# Keyboard_on_board.net
KiCad netlist of a schematic drawn in Altium Designer
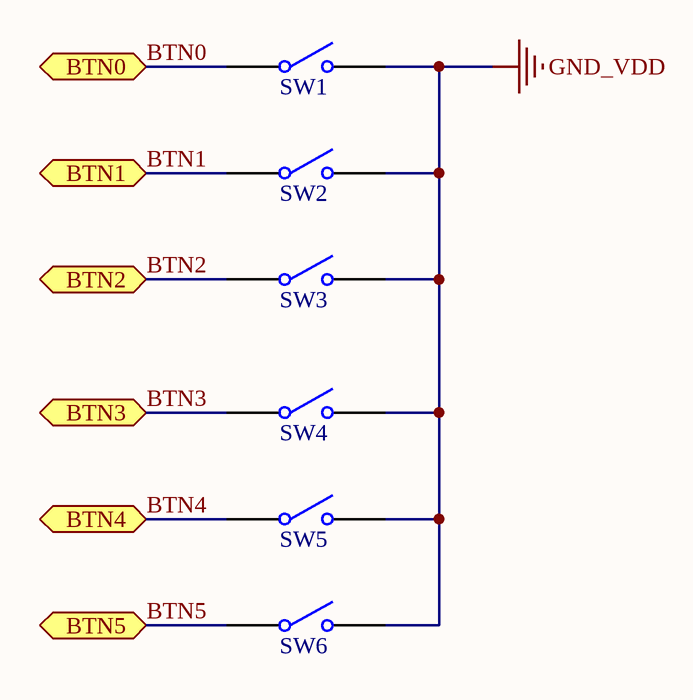
[diagram p0: Keyboard_on_board.SchDoc]

(export (version "E")
  (design (tool "Eeschema 10.0.6"))
  (components
    (comp (ref "SW1")
      (value "\"OK\"")
      (footprint "KAN1211")
      (description "Single-Pole, Single-Throw Switch")
      (fields (field (name "PUBLISHER") "Altium Limited"))
      (libsource (lib "Quasar ARM") (part "TACT Switch"))
    )
    (comp (ref "SW2")
      (value "\"Right\"")
      (footprint "KAN1211")
      (description "Single-Pole, Single-Throw Switch")
      (fields (field (name "PUBLISHER") "Altium Limited"))
      (libsource (lib "Quasar ARM") (part "TACT Switch"))
    )
    (comp (ref "SW3")
      (value "\"Down\"")
      (footprint "KAN1211")
      (description "Single-Pole, Single-Throw Switch")
      (fields (field (name "PUBLISHER") "Altium Limited"))
      (libsource (lib "Quasar ARM") (part "TACT Switch"))
    )
    (comp (ref "SW4")
      (value "\"Up\"")
      (footprint "KAN1211")
      (description "Single-Pole, Single-Throw Switch")
      (fields (field (name "PUBLISHER") "Altium Limited"))
      (libsource (lib "Quasar ARM") (part "TACT Switch"))
    )
    (comp (ref "SW5")
      (value "\"Left\"")
      (footprint "KAN1211")
      (description "Single-Pole, Single-Throw Switch")
      (fields (field (name "PUBLISHER") "Altium Limited"))
      (libsource (lib "Quasar ARM") (part "TACT Switch"))
    )
    (comp (ref "SW6")
      (value "\"Menu / Esc\"")
      (footprint "KAN1211")
      (description "Single-Pole, Single-Throw Switch")
      (fields (field (name "PUBLISHER") "Altium Limited"))
      (libsource (lib "Quasar ARM") (part "TACT Switch"))
    )
  )
  (nets
    (net (code "1") (name "/BTN0") (class "Default")
      (node (ref "SW1") (pin "1") (pinfunction "COMMON_1") (pintype "passive"))
    )
    (net (code "2") (name "/BTN1") (class "Default")
      (node (ref "SW2") (pin "1") (pinfunction "COMMON_1") (pintype "passive"))
    )
    (net (code "3") (name "/BTN2") (class "Default")
      (node (ref "SW3") (pin "1") (pinfunction "COMMON_1") (pintype "passive"))
    )
    (net (code "4") (name "/BTN3") (class "Default")
      (node (ref "SW4") (pin "1") (pinfunction "COMMON_1") (pintype "passive"))
    )
    (net (code "5") (name "/BTN4") (class "Default")
      (node (ref "SW5") (pin "1") (pinfunction "COMMON_1") (pintype "passive"))
    )
    (net (code "6") (name "/BTN5") (class "Default")
      (node (ref "SW6") (pin "1") (pinfunction "COMMON_1") (pintype "passive"))
    )
    (net (code "7") (name "GND_VDD") (class "Default")
      (node (ref "SW1") (pin "2") (pinfunction "NO_2") (pintype "passive"))
      (node (ref "SW2") (pin "2") (pinfunction "NO_2") (pintype "passive"))
      (node (ref "SW3") (pin "2") (pinfunction "NO_2") (pintype "passive"))
      (node (ref "SW4") (pin "2") (pinfunction "NO_2") (pintype "passive"))
      (node (ref "SW5") (pin "2") (pinfunction "NO_2") (pintype "passive"))
      (node (ref "SW6") (pin "2") (pinfunction "NO_2") (pintype "passive"))
    )
  )
)
